# 3V3_Block.net
KiCad netlist of a schematic drawn in Altium Designer
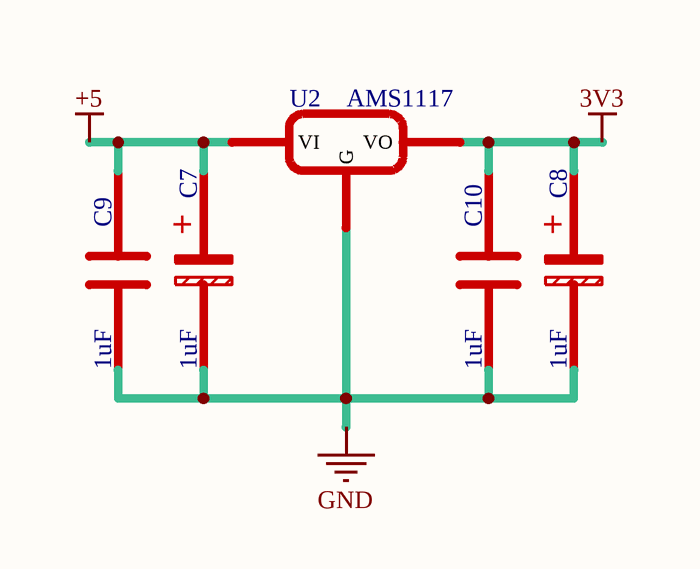
[diagram p0: 3V3_Block.SchDoc]

(export (version "E")
  (design (tool "Eeschema 10.0.6"))
  (components
    (comp (ref "C7")
      (value "1uF")
      (footprint "CAP-AL-4x5.4")
      (description "Aluminum Capacitor")
      (libsource (lib "CTAI-Library") (part "CAP-ALU"))
    )
    (comp (ref "C8")
      (value "1uF")
      (footprint "CAP-AL-4x5.4")
      (description "Aluminum Capacitor")
      (libsource (lib "CTAI-Library") (part "CAP-ALU"))
    )
    (comp (ref "C9")
      (value "1uF")
      (footprint "C0805")
      (description "Ceramic Capacitor")
      (libsource (lib "CTAI-Library") (part "CAP-CER"))
    )
    (comp (ref "C10")
      (value "1uF")
      (footprint "C0805")
      (description "Ceramic Capacitor")
      (libsource (lib "CTAI-Library") (part "CAP-CER"))
    )
    (comp (ref "U2")
      (value "AMS1117")
      (footprint "SOT-223")
      (description "Regulator intergated chip")
      (libsource (lib "CTAI-Library") (part "AMS1117"))
    )
  )
  (nets
    (net (code "1") (name "+5") (class "Default")
      (node (ref "C7") (pin "1") (pintype "passive"))
      (node (ref "C9") (pin "2") (pintype "passive"))
      (node (ref "U2") (pin "3") (pinfunction "VI_3") (pintype "passive"))
    )
    (net (code "2") (name "3V3") (class "Default")
      (node (ref "C10") (pin "2") (pintype "passive"))
      (node (ref "C8") (pin "1") (pintype "passive"))
      (node (ref "U2") (pin "2") (pinfunction "VO_2") (pintype "passive"))
    )
    (net (code "3") (name "GND") (class "Default")
      (node (ref "C10") (pin "1") (pintype "passive"))
      (node (ref "C7") (pin "2") (pintype "passive"))
      (node (ref "C8") (pin "2") (pintype "passive"))
      (node (ref "C9") (pin "1") (pintype "passive"))
      (node (ref "U2") (pin "1") (pinfunction "G_1") (pintype "passive"))
    )
  )
)
